# 19V_Converter.net
KiCad netlist of a schematic drawn in Altium Designer
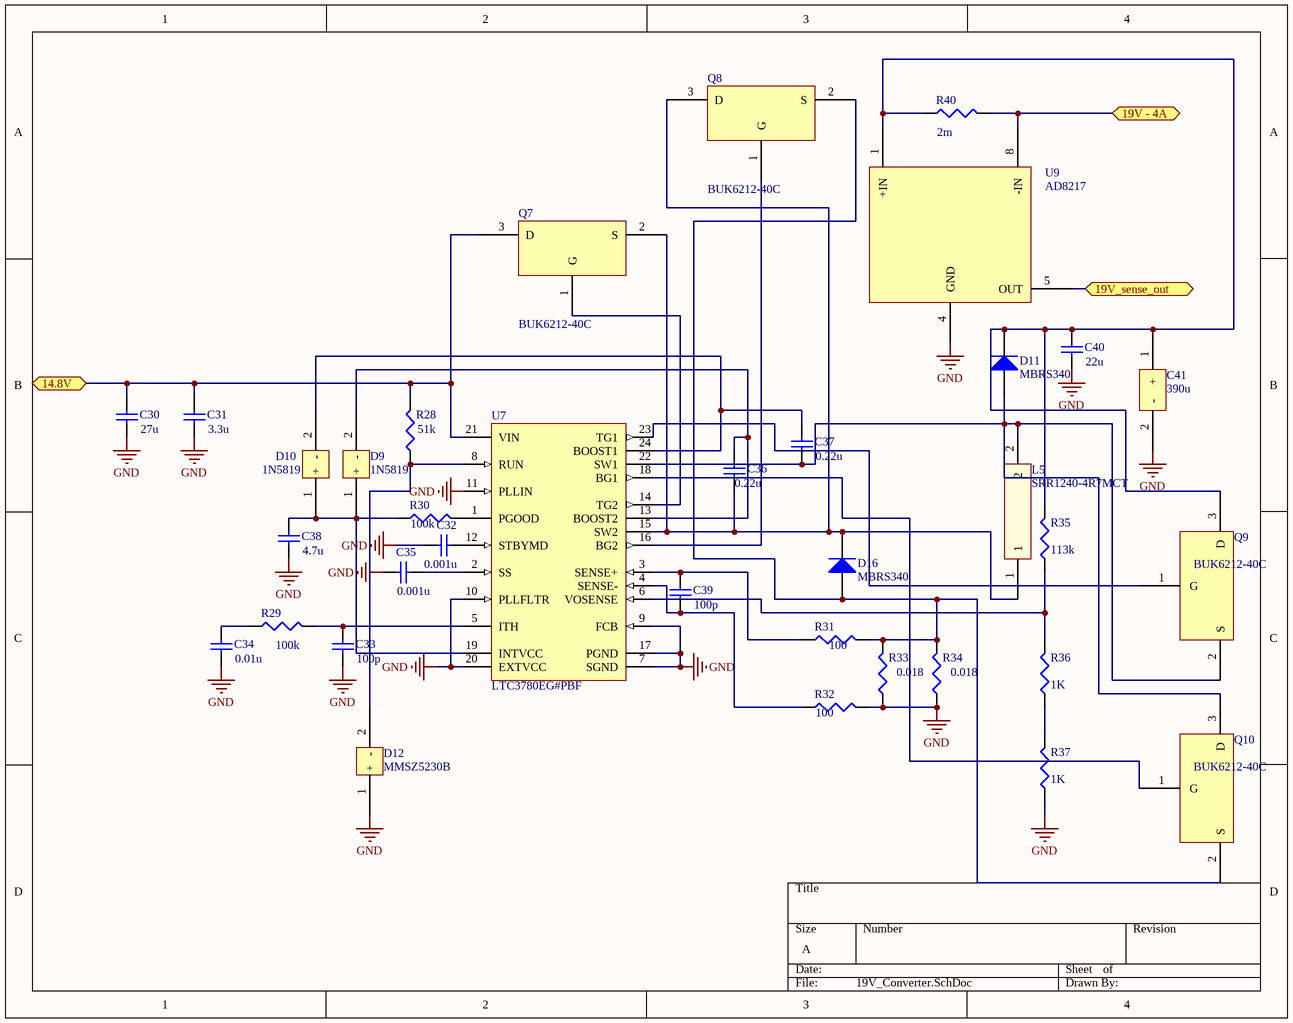
[diagram p0: 19V_Converter.SchDoc]

(export (version "E")
  (design (tool "Eeschema 10.0.6"))
  (components
    (comp (ref "C30")
      (value "27u")
      (footprint "C1206")
      (description "Capacitor (Semiconductor SIM Model)")
      (fields (field (name "Comment") "Cap Semi") (field (name "PUBLISHER") "Altium Limited"))
      (libsource (lib "Miscellaneous Devices") (part "Cap Semi"))
    )
    (comp (ref "C31")
      (value "3.3u")
      (footprint "C1206")
      (description "Capacitor (Semiconductor SIM Model)")
      (fields (field (name "Comment") "Cap Semi") (field (name "PUBLISHER") "Altium Limited"))
      (libsource (lib "Miscellaneous Devices") (part "Cap Semi"))
    )
    (comp (ref "C32")
      (value "0.001u")
      (footprint "C1206")
      (description "Capacitor (Semiconductor SIM Model)")
      (fields (field (name "Comment") "Cap Semi") (field (name "PUBLISHER") "Altium Limited"))
      (libsource (lib "Miscellaneous Devices") (part "Cap Semi"))
    )
    (comp (ref "C33")
      (value "100p")
      (footprint "C1206")
      (description "Capacitor (Semiconductor SIM Model)")
      (fields (field (name "Comment") "Cap Semi") (field (name "PUBLISHER") "Altium Limited"))
      (libsource (lib "Miscellaneous Devices") (part "Cap Semi"))
    )
    (comp (ref "C34")
      (value "0.01u")
      (footprint "C1206")
      (description "Capacitor (Semiconductor SIM Model)")
      (fields (field (name "Comment") "Cap Semi") (field (name "PUBLISHER") "Altium Limited"))
      (libsource (lib "Miscellaneous Devices") (part "Cap Semi"))
    )
    (comp (ref "C35")
      (value "0.001u")
      (footprint "C1206")
      (description "Capacitor (Semiconductor SIM Model)")
      (fields (field (name "Comment") "Cap Semi") (field (name "PUBLISHER") "Altium Limited"))
      (libsource (lib "Miscellaneous Devices") (part "Cap Semi"))
    )
    (comp (ref "C36")
      (value "0.22u")
      (footprint "C1206")
      (description "Capacitor (Semiconductor SIM Model)")
      (fields (field (name "Comment") "Cap Semi") (field (name "PUBLISHER") "Altium Limited"))
      (libsource (lib "Miscellaneous Devices") (part "Cap Semi"))
    )
    (comp (ref "C37")
      (value "0.22u")
      (footprint "C1206")
      (description "Capacitor (Semiconductor SIM Model)")
      (fields (field (name "Comment") "Cap Semi") (field (name "PUBLISHER") "Altium Limited"))
      (libsource (lib "Miscellaneous Devices") (part "Cap Semi"))
    )
    (comp (ref "C38")
      (value "4.7u")
      (footprint "C1206")
      (description "Capacitor (Semiconductor SIM Model)")
      (fields (field (name "Comment") "Cap Semi") (field (name "PUBLISHER") "Altium Limited"))
      (libsource (lib "Miscellaneous Devices") (part "Cap Semi"))
    )
    (comp (ref "C39")
      (value "100p")
      (footprint "C1206")
      (description "Capacitor (Semiconductor SIM Model)")
      (fields (field (name "Comment") "Cap Semi") (field (name "PUBLISHER") "Altium Limited"))
      (libsource (lib "Miscellaneous Devices") (part "Cap Semi"))
    )
    (comp (ref "C40")
      (value "22u")
      (footprint "C1206")
      (description "Capacitor (Semiconductor SIM Model)")
      (fields (field (name "Comment") "Cap Semi") (field (name "PUBLISHER") "Altium Limited"))
      (libsource (lib "Miscellaneous Devices") (part "Cap Semi"))
    )
    (comp (ref "C41") (value "390u") (footprint "Alum_Cap") (libsource (lib "AluminumCap") (part "Alum_Cap")))
    (comp (ref "D9")
      (value "1N5819")
      (footprint "SOD-123")
      (libsource (lib "Diode (1N5819)") (part "Component_1"))
    )
    (comp (ref "D10")
      (value "1N5819")
      (footprint "SOD-123")
      (libsource (lib "Diode (1N5819)") (part "Component_1"))
    )
    (comp (ref "D11")
      (value "MBRS340")
      (footprint "SMC")
      (description "Default Diode")
      (fields (field (name "PUBLISHER") "Altium Limited"))
      (libsource (lib "Miscellaneous Devices") (part "Diode"))
    )
    (comp (ref "D12")
      (value "MMSZ5230B")
      (footprint "SOD-123")
      (libsource (lib "Diode (1N5819)") (part "Component_1"))
    )
    (comp (ref "D16")
      (value "MBRS340")
      (footprint "SMC")
      (description "Default Diode")
      (fields (field (name "PUBLISHER") "Altium Limited"))
      (libsource (lib "Miscellaneous Devices") (part "Diode"))
    )
    (comp (ref "L5")
      (value "SRR1240-4R7MCT")
      (footprint "INDP125125X45N")
      (libsource (lib "SRR1240-4R7MCT") (part "SRR1240-4R7MCT"))
    )
    (comp (ref "Q7")
      (value "BUK6212-40C")
      (footprint "SOT457P1000X238-3N")
      (libsource (lib "BUK6212-40C") (part "Component_1"))
    )
    (comp (ref "Q8")
      (value "BUK6212-40C")
      (footprint "SOT457P1000X238-3N")
      (libsource (lib "BUK6212-40C") (part "Component_1"))
    )
    (comp (ref "Q9")
      (value "BUK6212-40C")
      (footprint "SOT457P1000X238-3N")
      (libsource (lib "") (part "Component_1_1"))
    )
    (comp (ref "Q10")
      (value "BUK6212-40C")
      (footprint "SOT457P1000X238-3N")
      (libsource (lib "") (part "Component_1_1"))
    )
    (comp (ref "R28")
      (value "51k")
      (footprint "J1-0603")
      (description "Resistor")
      (fields (field (name "Comment") "Res3") (field (name "PUBLISHER") "Altium Limited"))
      (libsource (lib "Miscellaneous Devices") (part "Res3"))
    )
    (comp (ref "R29")
      (value "100k")
      (footprint "J1-0603")
      (description "Resistor")
      (fields (field (name "Comment") "Res3") (field (name "PUBLISHER") "Altium Limited"))
      (libsource (lib "Miscellaneous Devices") (part "Res3"))
    )
    (comp (ref "R30")
      (value "100k")
      (footprint "J1-0603")
      (description "Resistor")
      (fields (field (name "Comment") "Res3") (field (name "PUBLISHER") "Altium Limited"))
      (libsource (lib "Miscellaneous Devices") (part "Res3"))
    )
    (comp (ref "R31")
      (value "100")
      (footprint "J1-0603")
      (description "Resistor")
      (fields (field (name "Comment") "Res3") (field (name "PUBLISHER") "Altium Limited"))
      (libsource (lib "Miscellaneous Devices") (part "Res3"))
    )
    (comp (ref "R32")
      (value "100")
      (footprint "J1-0603")
      (description "Resistor")
      (fields (field (name "Comment") "Res3") (field (name "PUBLISHER") "Altium Limited"))
      (libsource (lib "Miscellaneous Devices") (part "Res3"))
    )
    (comp (ref "R33")
      (value "0.018")
      (footprint "J1-0603")
      (description "Resistor")
      (fields (field (name "Comment") "Res3") (field (name "PUBLISHER") "Altium Limited"))
      (libsource (lib "Miscellaneous Devices") (part "Res3"))
    )
    (comp (ref "R34")
      (value "0.018")
      (footprint "J1-0603")
      (description "Resistor")
      (fields (field (name "Comment") "Res3") (field (name "PUBLISHER") "Altium Limited"))
      (libsource (lib "Miscellaneous Devices") (part "Res3"))
    )
    (comp (ref "R35")
      (value "113k")
      (footprint "J1-0603")
      (description "Resistor")
      (fields (field (name "Comment") "Res3") (field (name "PUBLISHER") "Altium Limited"))
      (libsource (lib "Miscellaneous Devices") (part "Res3"))
    )
    (comp (ref "R36")
      (value "1K")
      (footprint "J1-0603")
      (description "Resistor")
      (fields (field (name "Comment") "Res3") (field (name "PUBLISHER") "Altium Limited"))
      (libsource (lib "Miscellaneous Devices") (part "Res3"))
    )
    (comp (ref "R37")
      (value "1K")
      (footprint "J1-0603")
      (description "Resistor")
      (fields (field (name "Comment") "Res3") (field (name "PUBLISHER") "Altium Limited"))
      (libsource (lib "Miscellaneous Devices") (part "Res3"))
    )
    (comp (ref "R40")
      (value "2m")
      (footprint "14-1210")
      (description "Resistor")
      (fields (field (name "Comment") "Res3") (field (name "PUBLISHER") "Altium Limited"))
      (libsource (lib "Miscellaneous Devices") (part "Res3"))
    )
    (comp (ref "U7")
      (value "LTC3780EG#PBF")
      (footprint "LT-G-24_N")
      (fields (field (name "MANUFACTURER") "Linear Technology"))
      (libsource (lib "Linear Technology Power Management Switching Regulator LTC1174-LTC3901") (part "LTC3780EG#PBF"))
    )
    (comp (ref "U9")
      (value "AD8217")
      (footprint "TSOP65P490X110-8N")
      (description "Current Shunt Moniter")
      (libsource (lib "AD8217") (part "Component_1"))
    )
  )
  (nets
    (net (code "1") (name "/14.8V") (class "Default")
      (node (ref "C30") (pin "2") (pinfunction "2_2") (pintype "passive"))
      (node (ref "C31") (pin "2") (pinfunction "2_2") (pintype "passive"))
      (node (ref "Q7") (pin "3") (pinfunction "D_3") (pintype "passive"))
      (node (ref "R28") (pin "2") (pinfunction "2_2") (pintype "passive"))
      (node (ref "U7") (pin "21") (pinfunction "VIN_21") (pintype "power_in"))
    )
    (net (code "2") (name "/19V - 4A") (class "Default")
      (node (ref "R40") (pin "2") (pinfunction "2_2") (pintype "passive"))
      (node (ref "U9") (pin "8") (pinfunction "-IN_8") (pintype "passive"))
    )
    (net (code "3") (name "/19V_sense_out") (class "Default")
      (node (ref "U9") (pin "5") (pinfunction "OUT_5") (pintype "passive"))
    )
    (net (code "4") (name "GND") (class "Default")
      (node (ref "C30") (pin "1") (pinfunction "1_1") (pintype "passive"))
      (node (ref "C31") (pin "1") (pinfunction "1_1") (pintype "passive"))
      (node (ref "C32") (pin "1") (pinfunction "1_1") (pintype "passive"))
      (node (ref "C33") (pin "1") (pinfunction "1_1") (pintype "passive"))
      (node (ref "C34") (pin "1") (pinfunction "1_1") (pintype "passive"))
      (node (ref "C35") (pin "1") (pinfunction "1_1") (pintype "passive"))
      (node (ref "C38") (pin "1") (pinfunction "1_1") (pintype "passive"))
      (node (ref "C40") (pin "1") (pinfunction "1_1") (pintype "passive"))
      (node (ref "C41") (pin "2") (pinfunction "-_2") (pintype "passive"))
      (node (ref "D12") (pin "1") (pinfunction "+_1") (pintype "passive"))
      (node (ref "R32") (pin "2") (pinfunction "2_2") (pintype "passive"))
      (node (ref "R33") (pin "1") (pinfunction "1_1") (pintype "passive"))
      (node (ref "R34") (pin "1") (pinfunction "1_1") (pintype "passive"))
      (node (ref "R37") (pin "1") (pinfunction "1_1") (pintype "passive"))
      (node (ref "U7") (pin "10") (pinfunction "PLLFLTR_10") (pintype "input"))
      (node (ref "U7") (pin "11") (pinfunction "PLLIN_11") (pintype "input"))
      (node (ref "U7") (pin "17") (pinfunction "PGND_17") (pintype "power_in"))
      (node (ref "U7") (pin "20") (pinfunction "EXTVCC_20") (pintype "power_in"))
      (node (ref "U7") (pin "7") (pinfunction "SGND_7") (pintype "power_in"))
      (node (ref "U7") (pin "9") (pinfunction "FCB_9") (pintype "input"))
      (node (ref "U9") (pin "4") (pinfunction "GND_4") (pintype "passive"))
    )
    (net (code "5") (name "Net-(C34-Pad2)") (class "Default")
      (node (ref "C34") (pin "2") (pinfunction "2_2") (pintype "passive"))
      (node (ref "R29") (pin "1") (pinfunction "1_1") (pintype "passive"))
    )
    (net (code "6") (name "Net-(C41-+)") (class "Default")
      (node (ref "C40") (pin "2") (pinfunction "2_2") (pintype "passive"))
      (node (ref "C41") (pin "1") (pinfunction "+_1") (pintype "passive"))
      (node (ref "D11") (pin "2") (pinfunction "K_2") (pintype "passive"))
      (node (ref "Q9") (pin "3") (pinfunction "D_3") (pintype "passive"))
      (node (ref "R35") (pin "2") (pinfunction "2_2") (pintype "passive"))
      (node (ref "R40") (pin "1") (pinfunction "1_1") (pintype "passive"))
      (node (ref "U9") (pin "1") (pinfunction "+IN_1") (pintype "passive"))
    )
    (net (code "7") (name "Net-(D9--)") (class "Default")
      (node (ref "C36") (pin "2") (pinfunction "2_2") (pintype "passive"))
      (node (ref "D9") (pin "2") (pinfunction "-_2") (pintype "passive"))
      (node (ref "U7") (pin "13") (pinfunction "BOOST2_13") (pintype "passive"))
    )
    (net (code "8") (name "Net-(D10-+)") (class "Default")
      (node (ref "C38") (pin "2") (pinfunction "2_2") (pintype "passive"))
      (node (ref "D10") (pin "1") (pinfunction "+_1") (pintype "passive"))
      (node (ref "D9") (pin "1") (pinfunction "+_1") (pintype "passive"))
      (node (ref "R30") (pin "1") (pinfunction "1_1") (pintype "passive"))
      (node (ref "U7") (pin "19") (pinfunction "INTVCC_19") (pintype "power_in"))
    )
    (net (code "9") (name "Net-(D10--)") (class "Default")
      (node (ref "C37") (pin "2") (pinfunction "2_2") (pintype "passive"))
      (node (ref "D10") (pin "2") (pinfunction "-_2") (pintype "passive"))
      (node (ref "U7") (pin "24") (pinfunction "BOOST1_24") (pintype "passive"))
    )
    (net (code "10") (name "Net-(D11-A)") (class "Default")
      (node (ref "C37") (pin "1") (pinfunction "1_1") (pintype "passive"))
      (node (ref "D11") (pin "1") (pinfunction "A_1") (pintype "passive"))
      (node (ref "L5") (pin "2") (pinfunction "2_2") (pintype "passive"))
      (node (ref "Q10") (pin "3") (pinfunction "D_3") (pintype "passive"))
      (node (ref "Q9") (pin "2") (pinfunction "S_2") (pintype "passive"))
      (node (ref "U7") (pin "22") (pinfunction "SW1_22") (pintype "passive"))
    )
    (net (code "11") (name "Net-(D12--)") (class "Default")
      (node (ref "D12") (pin "2") (pinfunction "-_2") (pintype "passive"))
      (node (ref "R28") (pin "1") (pinfunction "1_1") (pintype "passive"))
      (node (ref "U7") (pin "8") (pinfunction "RUN_8") (pintype "input"))
    )
    (net (code "12") (name "Net-(D16-A)") (class "Default")
      (node (ref "D16") (pin "1") (pinfunction "A_1") (pintype "passive"))
      (node (ref "Q10") (pin "2") (pinfunction "S_2") (pintype "passive"))
      (node (ref "Q8") (pin "2") (pinfunction "S_2") (pintype "passive"))
      (node (ref "R31") (pin "2") (pinfunction "2_2") (pintype "passive"))
      (node (ref "R33") (pin "2") (pinfunction "2_2") (pintype "passive"))
      (node (ref "R34") (pin "2") (pinfunction "2_2") (pintype "passive"))
    )
    (net (code "13") (name "Net-(D16-K)") (class "Default")
      (node (ref "C36") (pin "1") (pinfunction "1_1") (pintype "passive"))
      (node (ref "D16") (pin "2") (pinfunction "K_2") (pintype "passive"))
      (node (ref "L5") (pin "1") (pinfunction "1_1") (pintype "passive"))
      (node (ref "Q7") (pin "2") (pinfunction "S_2") (pintype "passive"))
      (node (ref "Q8") (pin "3") (pinfunction "D_3") (pintype "passive"))
      (node (ref "U7") (pin "15") (pinfunction "SW2_15") (pintype "passive"))
    )
    (net (code "14") (name "Net-(Q7-G)") (class "Default")
      (node (ref "Q7") (pin "1") (pinfunction "G_1") (pintype "passive"))
      (node (ref "U7") (pin "14") (pinfunction "TG2_14") (pintype "output"))
    )
    (net (code "15") (name "Net-(Q8-G)") (class "Default")
      (node (ref "Q8") (pin "1") (pinfunction "G_1") (pintype "passive"))
      (node (ref "U7") (pin "16") (pinfunction "BG2_16") (pintype "output"))
    )
    (net (code "16") (name "Net-(Q9-G)") (class "Default")
      (node (ref "Q9") (pin "1") (pinfunction "G_1") (pintype "passive"))
      (node (ref "U7") (pin "23") (pinfunction "TG1_23") (pintype "output"))
    )
    (net (code "17") (name "Net-(Q10-G)") (class "Default")
      (node (ref "Q10") (pin "1") (pinfunction "G_1") (pintype "passive"))
      (node (ref "U7") (pin "18") (pinfunction "BG1_18") (pintype "output"))
    )
    (net (code "18") (name "Net-(R36-Pad1)") (class "Default")
      (node (ref "R36") (pin "1") (pinfunction "1_1") (pintype "passive"))
      (node (ref "R37") (pin "2") (pinfunction "2_2") (pintype "passive"))
    )
    (net (code "19") (name "Net-(U7-ITH)") (class "Default")
      (node (ref "C33") (pin "2") (pinfunction "2_2") (pintype "passive"))
      (node (ref "R29") (pin "2") (pinfunction "2_2") (pintype "passive"))
      (node (ref "U7") (pin "5") (pinfunction "ITH_5") (pintype "passive"))
    )
    (net (code "20") (name "Net-(U7-PGOOD)") (class "Default")
      (node (ref "R30") (pin "2") (pinfunction "2_2") (pintype "passive"))
      (node (ref "U7") (pin "1") (pinfunction "PGOOD_1") (pintype "open_collector"))
    )
    (net (code "21") (name "Net-(U7-SENSE+)") (class "Default")
      (node (ref "C39") (pin "2") (pinfunction "2_2") (pintype "passive"))
      (node (ref "R31") (pin "1") (pinfunction "1_1") (pintype "passive"))
      (node (ref "U7") (pin "3") (pinfunction "SENSE+_3") (pintype "input"))
    )
    (net (code "22") (name "Net-(U7-SENSE-)") (class "Default")
      (node (ref "C39") (pin "1") (pinfunction "1_1") (pintype "passive"))
      (node (ref "R32") (pin "1") (pinfunction "1_1") (pintype "passive"))
      (node (ref "U7") (pin "4") (pinfunction "SENSE-_4") (pintype "input"))
    )
    (net (code "23") (name "Net-(U7-SS)") (class "Default")
      (node (ref "C35") (pin "2") (pinfunction "2_2") (pintype "passive"))
      (node (ref "U7") (pin "2") (pinfunction "SS_2") (pintype "input"))
    )
    (net (code "24") (name "Net-(U7-STBYMD)") (class "Default")
      (node (ref "C32") (pin "2") (pinfunction "2_2") (pintype "passive"))
      (node (ref "U7") (pin "12") (pinfunction "STBYMD_12") (pintype "input"))
    )
    (net (code "25") (name "Net-(U7-VOSENSE)") (class "Default")
      (node (ref "R35") (pin "1") (pinfunction "1_1") (pintype "passive"))
      (node (ref "R36") (pin "2") (pinfunction "2_2") (pintype "passive"))
      (node (ref "U7") (pin "6") (pinfunction "VOSENSE_6") (pintype "input"))
    )
  )
)
